# sunbeamB.net
KiCad netlist of a schematic drawn in EAGLE
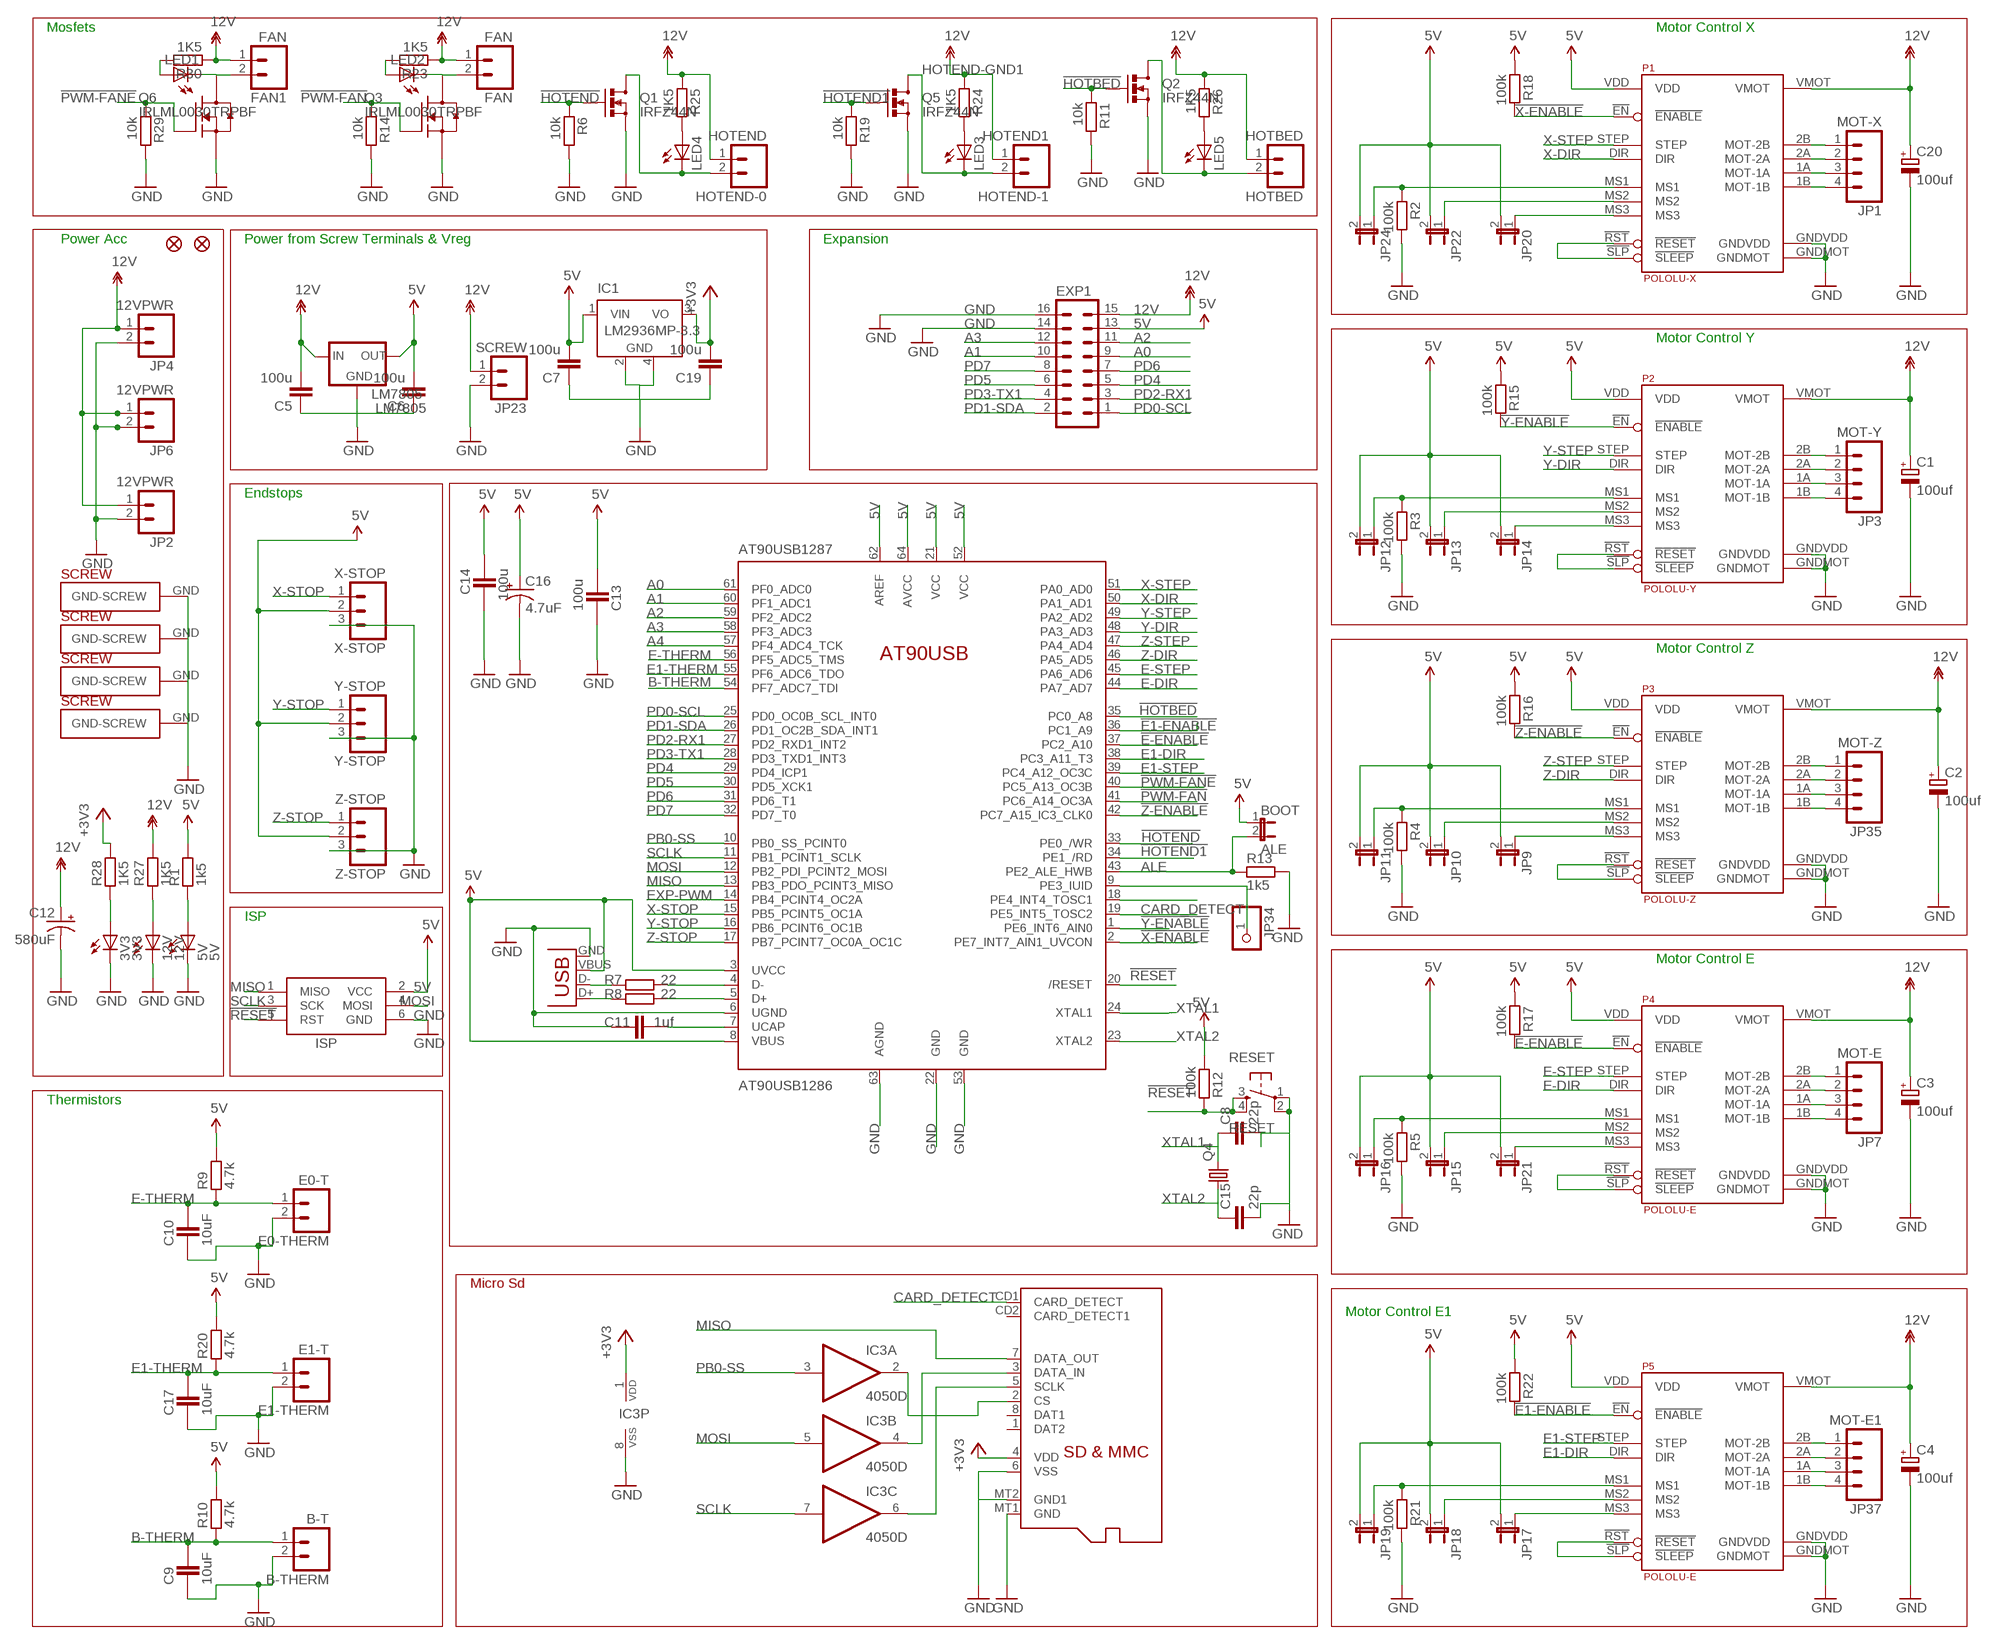
[diagram p0: schematic, sheet 1]

(export (version "E")
  (design (tool "Eeschema 10.0.6"))
  (components
    (comp (ref "3V3")
      (value "3V3")
      (footprint "eagle-import:CHIPLED_0805")
      (libsource (lib "eagle-import") (part "LEDCHIPLED_0805"))
    )
    (comp (ref "5V")
      (value "5V")
      (footprint "eagle-import:CHIPLED_0805")
      (libsource (lib "eagle-import") (part "LEDCHIPLED_0805"))
    )
    (comp (ref "12V")
      (value "12V")
      (footprint "eagle-import:CHIPLED_0805")
      (libsource (lib "eagle-import") (part "LEDCHIPLED_0805"))
    )
    (comp (ref "AT90USB1287")
      (value "AT90USB1286")
      (footprint "eagle-import:TQFP64-2")
      (libsource (lib "eagle-import") (part "AT90USB"))
    )
    (comp (ref "B-THERM")
      (value "B-T")
      (footprint "eagle-import:MOLEX-1X2")
      (libsource (lib "eagle-import") (part "M02POLAR"))
    )
    (comp (ref "BOOT")
      (value "ALE")
      (footprint "eagle-import:1X02")
      (libsource (lib "eagle-import") (part "JUMPER-2PTH"))
    )
    (comp (ref "C1")
      (value "100uf")
      (footprint "eagle-import:UD-6,3X7,7_NICHICON")
      (libsource (lib "eagle-import") (part "CPOL-EUUD-6,3X7,7"))
    )
    (comp (ref "C2")
      (value "100uf")
      (footprint "eagle-import:UD-6,3X7,7_NICHICON")
      (libsource (lib "eagle-import") (part "CPOL-EUUD-6,3X7,7"))
    )
    (comp (ref "C3")
      (value "100uf")
      (footprint "eagle-import:UD-6,3X7,7_NICHICON")
      (libsource (lib "eagle-import") (part "CPOL-EUUD-6,3X7,7"))
    )
    (comp (ref "C4")
      (value "100uf")
      (footprint "eagle-import:UD-6,3X7,7_NICHICON")
      (libsource (lib "eagle-import") (part "CPOL-EUUD-6,3X7,7"))
    )
    (comp (ref "C5")
      (value "100u")
      (footprint "eagle-import:C0805")
      (libsource (lib "eagle-import") (part "C-EUC0805"))
    )
    (comp (ref "C6")
      (value "100u")
      (footprint "eagle-import:C0805")
      (libsource (lib "eagle-import") (part "C-EUC0805"))
    )
    (comp (ref "C7")
      (value "100u")
      (footprint "eagle-import:C0805")
      (libsource (lib "eagle-import") (part "C-EUC0805"))
    )
    (comp (ref "C8")
      (value "22p")
      (footprint "eagle-import:C0805")
      (libsource (lib "eagle-import") (part "C-EUC0805"))
    )
    (comp (ref "C9")
      (value "10uF")
      (footprint "eagle-import:CAPC2012X145AN")
      (libsource (lib "eagle-import") (part "CAPACITOR_0805"))
    )
    (comp (ref "C10")
      (value "10uF")
      (footprint "eagle-import:CAPC2012X145AN")
      (libsource (lib "eagle-import") (part "CAPACITOR_0805"))
    )
    (comp (ref "C11")
      (value "1uf")
      (footprint "eagle-import:CAPC2012X145AN")
      (libsource (lib "eagle-import") (part "CAPACITOR_0805"))
    )
    (comp (ref "C12")
      (value "580uF")
      (footprint "eagle-import:CPOL-RADIAL-1000UF-25V")
      (libsource (lib "eagle-import") (part "CAP_POLPTH4"))
    )
    (comp (ref "C13")
      (value "100u")
      (footprint "eagle-import:CAPC2012X145AN")
      (libsource (lib "eagle-import") (part "CAPACITOR_0805"))
    )
    (comp (ref "C14")
      (value "100u")
      (footprint "eagle-import:CAPC2012X145AN")
      (libsource (lib "eagle-import") (part "CAPACITOR_0805"))
    )
    (comp (ref "C15")
      (value "22p")
      (footprint "eagle-import:C0805")
      (libsource (lib "eagle-import") (part "C-EUC0805"))
    )
    (comp (ref "C16")
      (value "4.7uF")
      (footprint "eagle-import:CPOL-RADIAL-10UF-25V")
      (libsource (lib "eagle-import") (part "CAP_POLPTH2"))
    )
    (comp (ref "C17")
      (value "10uF")
      (footprint "eagle-import:CAPC2012X145AN")
      (libsource (lib "eagle-import") (part "CAPACITOR_0805"))
    )
    (comp (ref "C19")
      (value "100u")
      (footprint "eagle-import:C0805")
      (libsource (lib "eagle-import") (part "C-EUC0805"))
    )
    (comp (ref "C20")
      (value "100uf")
      (footprint "eagle-import:UD-6,3X7,7_NICHICON")
      (libsource (lib "eagle-import") (part "CPOL-EUUD-6,3X7,7"))
    )
    (comp (ref "E0-THERM")
      (value "E0-T")
      (footprint "eagle-import:MOLEX-1X2")
      (libsource (lib "eagle-import") (part "M02POLAR"))
    )
    (comp (ref "E1-THERM")
      (value "E1-T")
      (footprint "eagle-import:MOLEX-1X2")
      (libsource (lib "eagle-import") (part "M02POLAR"))
    )
    (comp (ref "EXP1")
      (value "MA08-2")
      (footprint "eagle-import:MA08-2")
      (libsource (lib "eagle-import") (part "MA08-2"))
    )
    (comp (ref "FAN")
      (value "FAN")
      (footprint "eagle-import:MOLEX-1X2")
      (libsource (lib "eagle-import") (part "M02POLAR"))
    )
    (comp (ref "FAN1")
      (value "FAN")
      (footprint "eagle-import:MOLEX-1X2")
      (libsource (lib "eagle-import") (part "M02POLAR"))
    )
    (comp (ref "HOTBED")
      (value "HOTBED")
      (footprint "eagle-import:SCREWTERMINAL-5MM-2")
      (libsource (lib "eagle-import") (part "M025MM"))
    )
    (comp (ref "HOTEND-0")
      (value "HOTEND")
      (footprint "eagle-import:SCREWTERMINAL-5MM-2")
      (libsource (lib "eagle-import") (part "M025MM"))
    )
    (comp (ref "HOTEND-1")
      (value "HOTEND1")
      (footprint "eagle-import:SCREWTERMINAL-5MM-2")
      (libsource (lib "eagle-import") (part "M025MM"))
    )
    (comp (ref "IC1")
      (value "LM2936MP-3.3")
      (footprint "eagle-import:SOT223")
      (fields (field (name "MF") "NATIONAL SEMICONDUCTOR") (field (name "MPN") "LM2936MP-3.3/NOPB"))
      (libsource (lib "eagle-import") (part "LM2936MP?-3.3"))
    )
    (comp (ref "IC3")
      (value "4050D")
      (footprint "eagle-import:SO16")
      (libsource (lib "eagle-import") (part "4050D"))
    )
    (comp (ref "ISP")
      (value "ISP")
      (footprint "eagle-import:AVRISP")
      (libsource (lib "eagle-import") (part "AVRISP-6"))
    )
    (comp (ref "J1")
      (value "USB")
      (footprint "eagle-import:USB-B-PTH")
      (libsource (lib "eagle-import") (part "USBPTH"))
    )
    (comp (ref "JP1")
      (value "MOT-X")
      (footprint "eagle-import:MOLEX-1X4")
      (libsource (lib "eagle-import") (part "M04POLAR"))
    )
    (comp (ref "JP2")
      (value "12VPWR")
      (footprint "eagle-import:MOLEX-1X2")
      (libsource (lib "eagle-import") (part "M02POLAR"))
    )
    (comp (ref "JP3")
      (value "MOT-Y")
      (footprint "eagle-import:MOLEX-1X4")
      (libsource (lib "eagle-import") (part "M04POLAR"))
    )
    (comp (ref "JP4")
      (value "12VPWR")
      (footprint "eagle-import:MOLEX-1X2")
      (libsource (lib "eagle-import") (part "M02POLAR"))
    )
    (comp (ref "JP5")
      (value "FIDUCIAL1X2.5")
      (footprint "eagle-import:FIDUCIAL-1X2.5")
      (libsource (lib "eagle-import") (part "FIDUCIAL1X2.5"))
    )
    (comp (ref "JP6")
      (value "12VPWR")
      (footprint "eagle-import:MOLEX-1X2")
      (libsource (lib "eagle-import") (part "M02POLAR"))
    )
    (comp (ref "JP7")
      (value "MOT-E")
      (footprint "eagle-import:MOLEX-1X4")
      (libsource (lib "eagle-import") (part "M04POLAR"))
    )
    (comp (ref "JP8")
      (value "FIDUCIAL1X2.5")
      (footprint "eagle-import:FIDUCIAL-1X2.5")
      (libsource (lib "eagle-import") (part "FIDUCIAL1X2.5"))
    )
    (comp (ref "JP9")
      (value "JUMPER-2-OLDSMD-NO")
      (footprint "eagle-import:SJ_2S-NO")
      (libsource (lib "eagle-import") (part "JUMPER-2-OLDSMD-NO"))
    )
    (comp (ref "JP10")
      (value "JUMPER-2-OLDSMD-NO")
      (footprint "eagle-import:SJ_2S-NO")
      (libsource (lib "eagle-import") (part "JUMPER-2-OLDSMD-NO"))
    )
    (comp (ref "JP11")
      (value "JUMPER-2-OLDSMD-NO")
      (footprint "eagle-import:SJ_2S-NO")
      (libsource (lib "eagle-import") (part "JUMPER-2-OLDSMD-NO"))
    )
    (comp (ref "JP12")
      (value "JUMPER-2-OLDSMD-NO")
      (footprint "eagle-import:SJ_2S-NO")
      (libsource (lib "eagle-import") (part "JUMPER-2-OLDSMD-NO"))
    )
    (comp (ref "JP13")
      (value "JUMPER-2-OLDSMD-NO")
      (footprint "eagle-import:SJ_2S-NO")
      (libsource (lib "eagle-import") (part "JUMPER-2-OLDSMD-NO"))
    )
    (comp (ref "JP14")
      (value "JUMPER-2-OLDSMD-NO")
      (footprint "eagle-import:SJ_2S-NO")
      (libsource (lib "eagle-import") (part "JUMPER-2-OLDSMD-NO"))
    )
    (comp (ref "JP15")
      (value "JUMPER-2-OLDSMD-NO")
      (footprint "eagle-import:SJ_2S-NO")
      (libsource (lib "eagle-import") (part "JUMPER-2-OLDSMD-NO"))
    )
    (comp (ref "JP16")
      (value "JUMPER-2-OLDSMD-NO")
      (footprint "eagle-import:SJ_2S-NO")
      (libsource (lib "eagle-import") (part "JUMPER-2-OLDSMD-NO"))
    )
    (comp (ref "JP17")
      (value "JUMPER-2-OLDSMD-NO")
      (footprint "eagle-import:SJ_2S-NO")
      (libsource (lib "eagle-import") (part "JUMPER-2-OLDSMD-NO"))
    )
    (comp (ref "JP18")
      (value "JUMPER-2-OLDSMD-NO")
      (footprint "eagle-import:SJ_2S-NO")
      (libsource (lib "eagle-import") (part "JUMPER-2-OLDSMD-NO"))
    )
    (comp (ref "JP19")
      (value "JUMPER-2-OLDSMD-NO")
      (footprint "eagle-import:SJ_2S-NO")
      (libsource (lib "eagle-import") (part "JUMPER-2-OLDSMD-NO"))
    )
    (comp (ref "JP20")
      (value "JUMPER-2-OLDSMD-NO")
      (footprint "eagle-import:SJ_2S-NO")
      (libsource (lib "eagle-import") (part "JUMPER-2-OLDSMD-NO"))
    )
    (comp (ref "JP21")
      (value "JUMPER-2-OLDSMD-NO")
      (footprint "eagle-import:SJ_2S-NO")
      (libsource (lib "eagle-import") (part "JUMPER-2-OLDSMD-NO"))
    )
    (comp (ref "JP22")
      (value "JUMPER-2-OLDSMD-NO")
      (footprint "eagle-import:SJ_2S-NO")
      (libsource (lib "eagle-import") (part "JUMPER-2-OLDSMD-NO"))
    )
    (comp (ref "JP23")
      (value "SCREW")
      (footprint "eagle-import:SCREWTERMINAL-5MM-2")
      (libsource (lib "eagle-import") (part "M025MM"))
    )
    (comp (ref "JP24")
      (value "JUMPER-2-OLDSMD-NO")
      (footprint "eagle-import:SJ_2S-NO")
      (libsource (lib "eagle-import") (part "JUMPER-2-OLDSMD-NO"))
    )
    (comp (ref "JP34")
      (value "PINHD-1X1")
      (footprint "eagle-import:1X01")
      (libsource (lib "eagle-import") (part "PINHD-1X1"))
    )
    (comp (ref "JP35")
      (value "MOT-Z")
      (footprint "eagle-import:MOLEX-1X4")
      (libsource (lib "eagle-import") (part "M04POLAR"))
    )
    (comp (ref "JP37")
      (value "MOT-E1")
      (footprint "eagle-import:MOLEX-1X4")
      (libsource (lib "eagle-import") (part "M04POLAR"))
    )
    (comp (ref "LED1")
      (value "LEDCHIPLED_0805")
      (footprint "eagle-import:CHIPLED_0805")
      (libsource (lib "eagle-import") (part "LEDCHIPLED_0805"))
    )
    (comp (ref "LED2")
      (value "LEDCHIPLED_0805")
      (footprint "eagle-import:CHIPLED_0805")
      (libsource (lib "eagle-import") (part "LEDCHIPLED_0805"))
    )
    (comp (ref "LED3")
      (value "LEDCHIPLED_0805")
      (footprint "eagle-import:CHIPLED_0805")
      (libsource (lib "eagle-import") (part "LEDCHIPLED_0805"))
    )
    (comp (ref "LED4")
      (value "LEDCHIPLED_0805")
      (footprint "eagle-import:CHIPLED_0805")
      (libsource (lib "eagle-import") (part "LEDCHIPLED_0805"))
    )
    (comp (ref "LED5")
      (value "LEDCHIPLED_0805")
      (footprint "eagle-import:CHIPLED_0805")
      (libsource (lib "eagle-import") (part "LEDCHIPLED_0805"))
    )
    (comp (ref "LM7805")
      (value "LM7805")
      (footprint "eagle-import:78XXL-CUSTOM")
      (libsource (lib "eagle-import") (part "V_REG_78XX"))
    )
    (comp (ref "MICRO-SD")
      (value "MICROSD")
      (footprint "eagle-import:MICROSD")
      (libsource (lib "eagle-import") (part "MICROSD"))
    )
    (comp (ref "P1")
      (value "POLOLU-X")
      (footprint "eagle-import:POLOLU-ALLEGRO-PTH")
      (libsource (lib "eagle-import") (part "POLOLU-ALLEGRO"))
    )
    (comp (ref "P2")
      (value "POLOLU-Y")
      (footprint "eagle-import:POLOLU-ALLEGRO-PTH")
      (libsource (lib "eagle-import") (part "POLOLU-ALLEGRO"))
    )
    (comp (ref "P3")
      (value "POLOLU-Z")
      (footprint "eagle-import:POLOLU-ALLEGRO-PTH")
      (libsource (lib "eagle-import") (part "POLOLU-ALLEGRO"))
    )
    (comp (ref "P4")
      (value "POLOLU-E")
      (footprint "eagle-import:POLOLU-ALLEGRO-PTH")
      (libsource (lib "eagle-import") (part "POLOLU-ALLEGRO"))
    )
    (comp (ref "P5")
      (value "POLOLU-E")
      (footprint "eagle-import:POLOLU-ALLEGRO-PTH")
      (libsource (lib "eagle-import") (part "POLOLU-ALLEGRO"))
    )
    (comp (ref "Q1")
      (value "IRFZ44N")
      (footprint "eagle-import:TO220V")
      (libsource (lib "eagle-import") (part "MOSFET-NCHANNELPTH2"))
    )
    (comp (ref "Q2")
      (value "IRFZ44N")
      (footprint "eagle-import:TO220V")
      (libsource (lib "eagle-import") (part "MOSFET-NCHANNELPTH2"))
    )
    (comp (ref "Q3")
      (value "IRLML0030TRPBF")
      (footprint "eagle-import:SOT95P280X135-3N")
      (libsource (lib "eagle-import") (part "MOSFET-NCH_SOT-23"))
    )
    (comp (ref "Q4")
      (value "CRYSTALHC49UP")
      (footprint "eagle-import:HC49UP")
      (libsource (lib "eagle-import") (part "CRYSTALHC49UP"))
    )
    (comp (ref "Q5")
      (value "IRFZ44N")
      (footprint "eagle-import:TO220V")
      (libsource (lib "eagle-import") (part "MOSFET-NCHANNELPTH2"))
    )
    (comp (ref "Q6")
      (value "IRLML0030TRPBF")
      (footprint "eagle-import:SOT95P280X135-3N")
      (libsource (lib "eagle-import") (part "MOSFET-NCH_SOT-23"))
    )
    (comp (ref "R1")
      (value "1k5")
      (footprint "eagle-import:RESC2012X70N")
      (libsource (lib "eagle-import") (part "RESISTOR_0805"))
    )
    (comp (ref "R2")
      (value "100k")
      (footprint "eagle-import:RESC2012X70N")
      (libsource (lib "eagle-import") (part "RESISTOR_0805"))
    )
    (comp (ref "R3")
      (value "100k")
      (footprint "eagle-import:RESC2012X70N")
      (libsource (lib "eagle-import") (part "RESISTOR_0805"))
    )
    (comp (ref "R4")
      (value "100k")
      (footprint "eagle-import:RESC2012X70N")
      (libsource (lib "eagle-import") (part "RESISTOR_0805"))
    )
    (comp (ref "R5")
      (value "100k")
      (footprint "eagle-import:RESC2012X70N")
      (libsource (lib "eagle-import") (part "RESISTOR_0805"))
    )
    (comp (ref "R6")
      (value "10k")
      (footprint "eagle-import:RESC2012X70N")
      (libsource (lib "eagle-import") (part "RESISTOR_0805"))
    )
    (comp (ref "R7")
      (value "22")
      (footprint "eagle-import:RESC2012X70N")
      (libsource (lib "eagle-import") (part "RESISTOR_0805"))
    )
    (comp (ref "R8")
      (value "22")
      (footprint "eagle-import:RESC2012X70N")
      (libsource (lib "eagle-import") (part "RESISTOR_0805"))
    )
    (comp (ref "R9")
      (value "4.7k")
      (footprint "eagle-import:RESC2012X70N")
      (libsource (lib "eagle-import") (part "RESISTOR_0805"))
    )
    (comp (ref "R10")
      (value "4.7k")
      (footprint "eagle-import:RESC2012X70N")
      (libsource (lib "eagle-import") (part "RESISTOR_0805"))
    )
    (comp (ref "R11")
      (value "10k")
      (footprint "eagle-import:RESC2012X70N")
      (libsource (lib "eagle-import") (part "RESISTOR_0805"))
    )
    (comp (ref "R12")
      (value "100k")
      (footprint "eagle-import:RESC2012X70N")
      (libsource (lib "eagle-import") (part "RESISTOR_0805"))
    )
    (comp (ref "R13")
      (value "1k5")
      (footprint "eagle-import:RESC2012X70N")
      (libsource (lib "eagle-import") (part "RESISTOR_0805"))
    )
    (comp (ref "R14")
      (value "10k")
      (footprint "eagle-import:RESC2012X70N")
      (libsource (lib "eagle-import") (part "RESISTOR_0805"))
    )
    (comp (ref "R15")
      (value "100k")
      (footprint "eagle-import:RESC2012X70N")
      (libsource (lib "eagle-import") (part "RESISTOR_0805"))
    )
    (comp (ref "R16")
      (value "100k")
      (footprint "eagle-import:RESC2012X70N")
      (libsource (lib "eagle-import") (part "RESISTOR_0805"))
    )
    (comp (ref "R17")
      (value "100k")
      (footprint "eagle-import:RESC2012X70N")
      (libsource (lib "eagle-import") (part "RESISTOR_0805"))
    )
    (comp (ref "R18")
      (value "100k")
      (footprint "eagle-import:RESC2012X70N")
      (libsource (lib "eagle-import") (part "RESISTOR_0805"))
    )
    (comp (ref "R19")
      (value "10k")
      (footprint "eagle-import:RESC2012X70N")
      (libsource (lib "eagle-import") (part "RESISTOR_0805"))
    )
    (comp (ref "R20")
      (value "4.7k")
      (footprint "eagle-import:RESC2012X70N")
      (libsource (lib "eagle-import") (part "RESISTOR_0805"))
    )
    (comp (ref "R21")
      (value "100k")
      (footprint "eagle-import:RESC2012X70N")
      (libsource (lib "eagle-import") (part "RESISTOR_0805"))
    )
    (comp (ref "R22")
      (value "100k")
      (footprint "eagle-import:RESC2012X70N")
      (libsource (lib "eagle-import") (part "RESISTOR_0805"))
    )
    (comp (ref "R23")
      (value "1K5")
      (footprint "eagle-import:RESC2012X70N")
      (libsource (lib "eagle-import") (part "RESISTOR_0805"))
    )
    (comp (ref "R24")
      (value "1K5")
      (footprint "eagle-import:RESC2012X70N")
      (libsource (lib "eagle-import") (part "RESISTOR_0805"))
    )
    (comp (ref "R25")
      (value "1K5")
      (footprint "eagle-import:RESC2012X70N")
      (libsource (lib "eagle-import") (part "RESISTOR_0805"))
    )
    (comp (ref "R26")
      (value "1K5")
      (footprint "eagle-import:RESC2012X70N")
      (libsource (lib "eagle-import") (part "RESISTOR_0805"))
    )
    (comp (ref "R27")
      (value "1K5")
      (footprint "eagle-import:RESC2012X70N")
      (libsource (lib "eagle-import") (part "RESISTOR_0805"))
    )
    (comp (ref "R28")
      (value "1K5")
      (footprint "eagle-import:RESC2012X70N")
      (libsource (lib "eagle-import") (part "RESISTOR_0805"))
    )
    (comp (ref "R29")
      (value "10k")
      (footprint "eagle-import:RESC2012X70N")
      (libsource (lib "eagle-import") (part "RESISTOR_0805"))
    )
    (comp (ref "R30")
      (value "1K5")
      (footprint "eagle-import:RESC2012X70N")
      (libsource (lib "eagle-import") (part "RESISTOR_0805"))
    )
    (comp (ref "RESET")
      (value "RESET")
      (footprint "eagle-import:TACTILE-PTH")
      (libsource (lib "eagle-import") (part "TAC_SWITCHPTH"))
    )
    (comp (ref "U$47")
      (value "PLATED-SCREW")
      (footprint "eagle-import:PLATEDSCREW")
      (libsource (lib "eagle-import") (part "PLATED-SCREW"))
    )
    (comp (ref "U$48")
      (value "PLATED-SCREW")
      (footprint "eagle-import:PLATEDSCREW")
      (libsource (lib "eagle-import") (part "PLATED-SCREW"))
    )
    (comp (ref "U$49")
      (value "PLATED-SCREW")
      (footprint "eagle-import:PLATEDSCREW")
      (libsource (lib "eagle-import") (part "PLATED-SCREW"))
    )
    (comp (ref "U$50")
      (value "PLATED-SCREW")
      (footprint "eagle-import:PLATEDSCREW")
      (libsource (lib "eagle-import") (part "PLATED-SCREW"))
    )
    (comp (ref "X-STOP")
      (value "X-STOP")
      (footprint "eagle-import:MOLEX-1X3")
      (libsource (lib "eagle-import") (part "M03POLAR"))
    )
    (comp (ref "Y-STOP")
      (value "Y-STOP")
      (footprint "eagle-import:MOLEX-1X3")
      (libsource (lib "eagle-import") (part "M03POLAR"))
    )
    (comp (ref "Z-STOP")
      (value "Z-STOP")
      (footprint "eagle-import:MOLEX-1X3")
      (libsource (lib "eagle-import") (part "M03POLAR"))
    )
  )
  (nets
    (net (code "1") (name "+3V3") (class "Default")
      (node (ref "C19") (pin "2") (pinfunction "2_2") (pintype "passive"))
      (node (ref "IC1") (pin "3") (pinfunction "VO_3") (pintype "passive"))
      (node (ref "IC3") (pin "1") (pinfunction "VDD_1") (pintype "power_in"))
      (node (ref "MICRO-SD") (pin "4") (pinfunction "VDD_4") (pintype "power_in"))
      (node (ref "R28") (pin "2") (pinfunction "2_2") (pintype "passive"))
    )
    (net (code "2") (name "/A0") (class "Default")
      (node (ref "AT90USB1287") (pin "61") (pinfunction "PF0_ADC0_61") (pintype "bidirectional"))
      (node (ref "EXP1") (pin "9") (pinfunction "9_9") (pintype "passive"))
    )
    (net (code "3") (name "/A1") (class "Default")
      (node (ref "AT90USB1287") (pin "60") (pinfunction "PF1_ADC1_60") (pintype "bidirectional"))
      (node (ref "EXP1") (pin "10") (pinfunction "10_10") (pintype "passive"))
    )
    (net (code "4") (name "/A2") (class "Default")
      (node (ref "AT90USB1287") (pin "59") (pinfunction "PF2_ADC2_59") (pintype "bidirectional"))
      (node (ref "EXP1") (pin "11") (pinfunction "11_11") (pintype "passive"))
    )
    (net (code "5") (name "/A3") (class "Default")
      (node (ref "AT90USB1287") (pin "58") (pinfunction "PF3_ADC3_58") (pintype "bidirectional"))
      (node (ref "EXP1") (pin "12") (pinfunction "12_12") (pintype "passive"))
    )
    (net (code "6") (name "/A4") (class "Default")
      (node (ref "AT90USB1287") (pin "57") (pinfunction "PF4_ADC4_TCK_57") (pintype "bidirectional"))
    )
    (net (code "7") (name "/ALE") (class "Default")
      (node (ref "AT90USB1287") (pin "43") (pinfunction "PE2_ALE_HWB_43") (pintype "bidirectional"))
      (node (ref "BOOT") (pin "2") (pinfunction "2_2") (pintype "passive"))
      (node (ref "R13") (pin "1") (pinfunction "1_1") (pintype "passive"))
    )
    (net (code "8") (name "/B-THERM") (class "Default")
      (node (ref "AT90USB1287") (pin "54") (pinfunction "PF7_ADC7_TDI_54") (pintype "bidirectional"))
      (node (ref "B-THERM") (pin "1") (pinfunction "1_1") (pintype "passive"))
      (node (ref "C9") (pin "2") (pinfunction "2_2") (pintype "passive"))
      (node (ref "R10") (pin "1") (pinfunction "1_1") (pintype "passive"))
    )
    (net (code "9") (name "/CARD_DETECT") (class "Default")
      (node (ref "AT90USB1287") (pin "19") (pinfunction "PE5_INT5_TOSC2_19") (pintype "bidirectional"))
      (node (ref "MICRO-SD") (pin "CD1") (pinfunction "CARD_DETECT_CD1") (pintype "passive"))
    )
    (net (code "10") (name "/E-DIR") (class "Default")
      (node (ref "AT90USB1287") (pin "44") (pinfunction "PA7_AD7_44") (pintype "bidirectional"))
      (node (ref "P4") (pin "DIR") (pinfunction "DIR_DIR") (pintype "bidirectional"))
    )
    (net (code "11") (name "/E-STEP") (class "Default")
      (node (ref "AT90USB1287") (pin "45") (pinfunction "PA6_AD6_45") (pintype "bidirectional"))
      (node (ref "P4") (pin "STEP") (pinfunction "STEP_STEP") (pintype "bidirectional"))
    )
    (net (code "12") (name "/E-THERM") (class "Default")
      (node (ref "AT90USB1287") (pin "56") (pinfunction "PF5_ADC5_TMS_56") (pintype "bidirectional"))
      (node (ref "C10") (pin "2") (pinfunction "2_2") (pintype "passive"))
      (node (ref "E0-THERM") (pin "1") (pinfunction "1_1") (pintype "passive"))
      (node (ref "R9") (pin "1") (pinfunction "1_1") (pintype "passive"))
    )
    (net (code "13") (name "/E1-DIR") (class "Default")
      (node (ref "AT90USB1287") (pin "38") (pinfunction "PC3_A11_T3_38") (pintype "bidirectional"))
      (node (ref "P5") (pin "DIR") (pinfunction "DIR_DIR") (pintype "bidirectional"))
    )
    (net (code "14") (name "/E1-STEP") (class "Default")
      (node (ref "AT90USB1287") (pin "39") (pinfunction "PC4_A12_OC3C_39") (pintype "bidirectional"))
      (node (ref "P5") (pin "STEP") (pinfunction "STEP_STEP") (pintype "bidirectional"))
    )
    (net (code "15") (name "/E1-THERM") (class "Default")
      (node (ref "AT90USB1287") (pin "55") (pinfunction "PF6_ADC6_TDO_55") (pintype "bidirectional"))
      (node (ref "C17") (pin "2") (pinfunction "2_2") (pintype "passive"))
      (node (ref "E1-THERM") (pin "1") (pinfunction "1_1") (pintype "passive"))
      (node (ref "R20") (pin "1") (pinfunction "1_1") (pintype "passive"))
    )
    (net (code "16") (name "/EXP-PWM") (class "Default")
      (node (ref "AT90USB1287") (pin "14") (pinfunction "PB4_PCINT4_OC2A_14") (pintype "bidirectional"))
    )
    (net (code "17") (name "/HOTEND-GND1") (class "Default")
      (node (ref "HOTEND-1") (pin "2") (pinfunction "2_2") (pintype "passive"))
      (node (ref "LED3") (pin "C") (pinfunction "C_C") (pintype "passive"))
      (node (ref "Q5") (pin "2") (pinfunction "D_2") (pintype "passive"))
    )
    (net (code "18") (name "/MISO") (class "Default")
      (node (ref "AT90USB1287") (pin "13") (pinfunction "PB3_PDO_PCINT3_MISO_13") (pintype "bidirectional"))
      (node (ref "ISP") (pin "1") (pinfunction "MISO_1") (pintype "input"))
      (node (ref "MICRO-SD") (pin "7") (pinfunction "DATA_OUT_7") (pintype "output"))
    )
    (net (code "19") (name "/MOSI") (class "Default")
      (node (ref "AT90USB1287") (pin "12") (pinfunction "PB2_PDI_PCINT2_MOSI_12") (pintype "bidirectional"))
      (node (ref "IC3") (pin "5") (pinfunction "I_5") (pintype "input"))
      (node (ref "ISP") (pin "4") (pinfunction "MOSI_4") (pintype "output"))
    )
    (net (code "20") (name "/PB0-SS") (class "Default")
      (node (ref "AT90USB1287") (pin "10") (pinfunction "PB0_SS_PCINT0_10") (pintype "bidirectional"))
      (node (ref "IC3") (pin "3") (pinfunction "I_3") (pintype "input"))
    )
    (net (code "21") (name "/PD0-SCL") (class "Default")
      (node (ref "AT90USB1287") (pin "25") (pinfunction "PD0_OC0B_SCL_INT0_25") (pintype "bidirectional"))
      (node (ref "EXP1") (pin "1") (pinfunction "1_1") (pintype "passive"))
    )
    (net (code "22") (name "/PD1-SDA") (class "Default")
      (node (ref "AT90USB1287") (pin "26") (pinfunction "PD1_OC2B_SDA_INT1_26") (pintype "bidirectional"))
      (node (ref "EXP1") (pin "2") (pinfunction "2_2") (pintype "passive"))
    )
    (net (code "23") (name "/PD2-RX1") (class "Default")
      (node (ref "AT90USB1287") (pin "27") (pinfunction "PD2_RXD1_INT2_27") (pintype "bidirectional"))
      (node (ref "EXP1") (pin "3") (pinfunction "3_3") (pintype "passive"))
    )
    (net (code "24") (name "/PD3-TX1") (class "Default")
      (node (ref "AT90USB1287") (pin "28") (pinfunction "PD3_TXD1_INT3_28") (pintype "bidirectional"))
      (node (ref "EXP1") (pin "4") (pinfunction "4_4") (pintype "passive"))
    )
    (net (code "25") (name "/PD4") (class "Default")
      (node (ref "AT90USB1287") (pin "29") (pinfunction "PD4_ICP1_29") (pintype "bidirectional"))
      (node (ref "EXP1") (pin "5") (pinfunction "5_5") (pintype "passive"))
    )
    (net (code "26") (name "/PD5") (class "Default")
      (node (ref "AT90USB1287") (pin "30") (pinfunction "PD5_XCK1_30") (pintype "bidirectional"))
      (node (ref "EXP1") (pin "6") (pinfunction "6_6") (pintype "passive"))
    )
    (net (code "27") (name "/PD6") (class "Default")
      (node (ref "AT90USB1287") (pin "31") (pinfunction "PD6_T1_31") (pintype "bidirectional"))
      (node (ref "EXP1") (pin "7") (pinfunction "7_7") (pintype "passive"))
    )
    (net (code "28") (name "/PD7") (class "Default")
      (node (ref "AT90USB1287") (pin "32") (pinfunction "PD7_T0_32") (pintype "bidirectional"))
      (node (ref "EXP1") (pin "8") (pinfunction "8_8") (pintype "passive"))
    )
    (net (code "29") (name "/SCLK") (class "Default")
      (node (ref "AT90USB1287") (pin "11") (pinfunction "PB1_PCINT1_SCLK_11") (pintype "bidirectional"))
      (node (ref "IC3") (pin "7") (pinfunction "I_7") (pintype "input"))
      (node (ref "ISP") (pin "3") (pinfunction "SCK_3") (pintype "output"))
    )
    (net (code "30") (name "/X-DIR") (class "Default")
      (node (ref "AT90USB1287") (pin "50") (pinfunction "PA1_AD1_50") (pintype "bidirectional"))
      (node (ref "P1") (pin "DIR") (pinfunction "DIR_DIR") (pintype "bidirectional"))
    )
    (net (code "31") (name "/X-STEP") (class "Default")
      (node (ref "AT90USB1287") (pin "51") (pinfunction "PA0_AD0_51") (pintype "bidirectional"))
      (node (ref "P1") (pin "STEP") (pinfunction "STEP_STEP") (pintype "bidirectional"))
    )
    (net (code "32") (name "/X-STOP") (class "Default")
      (node (ref "AT90USB1287") (pin "15") (pinfunction "PB5_PCINT5_OC1A_15") (pintype "bidirectional"))
      (node (ref "X-STOP") (pin "1") (pinfunction "1_1") (pintype "passive"))
    )
    (net (code "33") (name "/XTAL1") (class "Default")
      (node (ref "AT90USB1287") (pin "24") (pinfunction "XTAL1_24") (pintype "passive"))
      (node (ref "C8") (pin "1") (pinfunction "1_1") (pintype "passive"))
      (node (ref "Q4") (pin "2") (pinfunction "2_2") (pintype "passive"))
    )
    (net (code "34") (name "/XTAL2") (class "Default")
      (node (ref "AT90USB1287") (pin "23") (pinfunction "XTAL2_23") (pintype "passive"))
      (node (ref "C15") (pin "1") (pinfunction "1_1") (pintype "passive"))
      (node (ref "Q4") (pin "1") (pinfunction "1_1") (pintype "passive"))
    )
    (net (code "35") (name "/Y-DIR") (class "Default")
      (node (ref "AT90USB1287") (pin "48") (pinfunction "PA3_AD3_48") (pintype "bidirectional"))
      (node (ref "P2") (pin "DIR") (pinfunction "DIR_DIR") (pintype "bidirectional"))
    )
    (net (code "36") (name "/Y-STEP") (class "Default")
      (node (ref "AT90USB1287") (pin "49") (pinfunction "PA2_AD2_49") (pintype "bidirectional"))
      (node (ref "P2") (pin "STEP") (pinfunction "STEP_STEP") (pintype "bidirectional"))
    )
    (net (code "37") (name "/Y-STOP") (class "Default")
      (node (ref "AT90USB1287") (pin "16") (pinfunction "PB6_PCINT6_OC1B_16") (pintype "bidirectional"))
      (node (ref "Y-STOP") (pin "1") (pinfunction "1_1") (pintype "passive"))
    )
    (net (code "38") (name "/Z-DIR") (class "Default")
      (node (ref "AT90USB1287") (pin "46") (pinfunction "PA5_AD5_46") (pintype "bidirectional"))
      (node (ref "P3") (pin "DIR") (pinfunction "DIR_DIR") (pintype "bidirectional"))
    )
    (net (code "39") (name "/Z-STEP") (class "Default")
      (node (ref "AT90USB1287") (pin "47") (pinfunction "PA4_AD4_47") (pintype "bidirectional"))
      (node (ref "P3") (pin "STEP") (pinfunction "STEP_STEP") (pintype "bidirectional"))
    )
    (net (code "40") (name "/Z-STOP") (class "Default")
      (node (ref "AT90USB1287") (pin "17") (pinfunction "PB7_PCINT7_OC0A_OC1C_17") (pintype "bidirectional"))
      (node (ref "Z-STOP") (pin "1") (pinfunction "1_1") (pintype "passive"))
    )
    (net (code "41") (name "/~{E-ENABLE}") (class "Default")
      (node (ref "AT90USB1287") (pin "37") (pinfunction "PC2_A10_37") (pintype "bidirectional"))
      (node (ref "P4") (pin "!EN") (pinfunction "~{ENABLE}_!EN") (pintype "input"))
      (node (ref "R17") (pin "2") (pinfunction "2_2") (pintype "passive"))
    )
    (net (code "42") (name "/~{E1-ENABLE}") (class "Default")
      (node (ref "AT90USB1287") (pin "36") (pinfunction "PC1_A9_36") (pintype "bidirectional"))
      (node (ref "P5") (pin "!EN") (pinfunction "~{ENABLE}_!EN") (pintype "input"))
      (node (ref "R22") (pin "2") (pinfunction "2_2") (pintype "passive"))
    )
    (net (code "43") (name "/~{HOTBED}") (class "Default")
      (node (ref "AT90USB1287") (pin "35") (pinfunction "PC0_A8_35") (pintype "bidirectional"))
      (node (ref "Q2") (pin "1") (pinfunction "G_1") (pintype "passive"))
      (node (ref "R11") (pin "1") (pinfunction "1_1") (pintype "passive"))
    )
    (net (code "44") (name "/~{HOTEND1}") (class "Default")
      (node (ref "AT90USB1287") (pin "34") (pinfunction "PE1_/RD_34") (pintype "bidirectional"))
      (node (ref "Q5") (pin "1") (pinfunction "G_1") (pintype "passive"))
      (node (ref "R19") (pin "1") (pinfunction "1_1") (pintype "passive"))
    )
    (net (code "45") (name "/~{HOTEND}") (class "Default")
      (node (ref "AT90USB1287") (pin "33") (pinfunction "PE0_/WR_33") (pintype "bidirectional"))
      (node (ref "Q1") (pin "1") (pinfunction "G_1") (pintype "passive"))
      (node (ref "R6") (pin "1") (pinfunction "1_1") (pintype "passive"))
    )
    (net (code "46") (name "/~{PWM-FANE}") (class "Default")
      (node (ref "AT90USB1287") (pin "40") (pinfunction "PC5_A13_OC3B_40") (pintype "bidirectional"))
      (node (ref "Q6") (pin "1") (pinfunction "G_1") (pintype "passive"))
      (node (ref "R29") (pin "1") (pinfunction "1_1") (pintype "passive"))
    )
    (net (code "47") (name "/~{PWM-FAN}") (class "Default")
      (node (ref "AT90USB1287") (pin "41") (pinfunction "PC6_A14_OC3A_41") (pintype "bidirectional"))
      (node (ref "Q3") (pin "1") (pinfunction "G_1") (pintype "passive"))
      (node (ref "R14") (pin "1") (pinfunction "1_1") (pintype "passive"))
    )
    (net (code "48") (name "/~{RESET}") (class "Default")
      (node (ref "AT90USB1287") (pin "20") (pinfunction "/RESET_20") (pintype "bidirectional"))
      (node (ref "ISP") (pin "5") (pinfunction "RST_5") (pintype "output"))
      (node (ref "R12") (pin "1") (pinfunction "1_1") (pintype "passive"))
      (node (ref "RESET") (pin "3") (pinfunction "3_3") (pintype "passive"))
      (node (ref "RESET") (pin "4") (pinfunction "4_4") (pintype "passive"))
    )
    (net (code "49") (name "/~{X-ENABLE}") (class "Default")
      (node (ref "AT90USB1287") (pin "2") (pinfunction "PE7_INT7_AIN1_UVCON_2") (pintype "bidirectional"))
      (node (ref "P1") (pin "!EN") (pinfunction "~{ENABLE}_!EN") (pintype "input"))
      (node (ref "R18") (pin "2") (pinfunction "2_2") (pintype "passive"))
    )
    (net (code "50") (name "/~{Y-ENABLE}") (class "Default")
      (node (ref "AT90USB1287") (pin "1") (pinfunction "PE6_INT6_AIN0_1") (pintype "bidirectional"))
      (node (ref "P2") (pin "!EN") (pinfunction "~{ENABLE}_!EN") (pintype "input"))
      (node (ref "R15") (pin "2") (pinfunction "2_2") (pintype "passive"))
    )
    (net (code "51") (name "/~{Z-ENABLE}") (class "Default")
      (node (ref "AT90USB1287") (pin "42") (pinfunction "PC7_A15_IC3_CLK0_42") (pintype "bidirectional"))
      (node (ref "P3") (pin "!EN") (pinfunction "~{ENABLE}_!EN") (pintype "input"))
      (node (ref "R16") (pin "2") (pinfunction "2_2") (pintype "passive"))
    )
    (net (code "52") (name "5V") (class "Default")
      (node (ref "AT90USB1287") (pin "21") (pinfunction "VCC_21") (pintype "power_in"))
      (node (ref "AT90USB1287") (pin "3") (pinfunction "UVCC_3") (pintype "power_in"))
      (node (ref "AT90USB1287") (pin "52") (pinfunction "VCC_52") (pintype "power_in"))
      (node (ref "AT90USB1287") (pin "62") (pinfunction "AREF_62") (pintype "power_in"))
      (node (ref "AT90USB1287") (pin "64") (pinfunction "AVCC_64") (pintype "power_in"))
      (node (ref "AT90USB1287") (pin "8") (pinfunction "VBUS_8") (pintype "bidirectional"))
      (node (ref "BOOT") (pin "1") (pinfunction "1_1") (pintype "passive"))
      (node (ref "C13") (pin "2") (pinfunction "2_2") (pintype "passive"))
      (node (ref "C14") (pin "1") (pinfunction "1_1") (pintype "passive"))
      (node (ref "C16") (pin "1") (pinfunction "+_1") (pintype "passive"))
      (node (ref "C6") (pin "2") (pinfunction "2_2") (pintype "passive"))
      (node (ref "C7") (pin "2") (pinfunction "2_2") (pintype "passive"))
      (node (ref "EXP1") (pin "13") (pinfunction "13_13") (pintype "passive"))
      (node (ref "IC1") (pin "1") (pinfunction "VIN_1") (pintype "input"))
      (node (ref "ISP") (pin "2") (pinfunction "VCC_2") (pintype "power_in"))
      (node (ref "J1") (pin "VBUS") (pinfunction "VBUS_VBUS") (pintype "bidirectional"))
      (node (ref "JP10") (pin "2") (pinfunction "2_2") (pintype "passive"))
      (node (ref "JP11") (pin "2") (pinfunction "2_2") (pintype "passive"))
      (node (ref "JP12") (pin "2") (pinfunction "2_2") (pintype "passive"))
      (node (ref "JP13") (pin "2") (pinfunction "2_2") (pintype "passive"))
      (node (ref "JP14") (pin "2") (pinfunction "2_2") (pintype "passive"))
      (node (ref "JP15") (pin "2") (pinfunction "2_2") (pintype "passive"))
      (node (ref "JP16") (pin "2") (pinfunction "2_2") (pintype "passive"))
      (node (ref "JP17") (pin "2") (pinfunction "2_2") (pintype "passive"))
      (node (ref "JP18") (pin "2") (pinfunction "2_2") (pintype "passive"))
      (node (ref "JP19") (pin "2") (pinfunction "2_2") (pintype "passive"))
      (node (ref "JP20") (pin "2") (pinfunction "2_2") (pintype "passive"))
      (node (ref "JP21") (pin "2") (pinfunction "2_2") (pintype "passive"))
      (node (ref "JP22") (pin "2") (pinfunction "2_2") (pintype "passive"))
      (node (ref "JP24") (pin "2") (pinfunction "2_2") (pintype "passive"))
      (node (ref "JP9") (pin "2") (pinfunction "2_2") (pintype "passive"))
      (node (ref "LM7805") (pin "OUT") (pinfunction "OUT_OUT") (pintype "output"))
      (node (ref "P1") (pin "VDD") (pinfunction "VDD_VDD") (pintype "power_in"))
      (node (ref "P2") (pin "VDD") (pinfunction "VDD_VDD") (pintype "power_in"))
      (node (ref "P3") (pin "VDD") (pinfunction "VDD_VDD") (pintype "power_in"))
      (node (ref "P4") (pin "VDD") (pinfunction "VDD_VDD") (pintype "power_in"))
      (node (ref "P5") (pin "VDD") (pinfunction "VDD_VDD") (pintype "power_in"))
      (node (ref "R1") (pin "2") (pinfunction "2_2") (pintype "passive"))
      (node (ref "R10") (pin "2") (pinfunction "2_2") (pintype "passive"))
      (node (ref "R12") (pin "2") (pinfunction "2_2") (pintype "passive"))
      (node (ref "R15") (pin "1") (pinfunction "1_1") (pintype "passive"))
      (node (ref "R16") (pin "1") (pinfunction "1_1") (pintype "passive"))
      (node (ref "R17") (pin "1") (pinfunction "1_1") (pintype "passive"))
      (node (ref "R18") (pin "1") (pinfunction "1_1") (pintype "passive"))
      (node (ref "R20") (pin "2") (pinfunction "2_2") (pintype "passive"))
      (node (ref "R22") (pin "1") (pinfunction "1_1") (pintype "passive"))
      (node (ref "R9") (pin "2") (pinfunction "2_2") (pintype "passive"))
      (node (ref "X-STOP") (pin "2") (pinfunction "2_2") (pintype "passive"))
      (node (ref "Y-STOP") (pin "2") (pinfunction "2_2") (pintype "passive"))
      (node (ref "Z-STOP") (pin "2") (pinfunction "2_2") (pintype "passive"))
    )
    (net (code "53") (name "12V") (class "Default")
      (node (ref "C1") (pin "+") (pinfunction "+_+") (pintype "passive"))
      (node (ref "C12") (pin "1") (pinfunction "+_1") (pintype "passive"))
      (node (ref "C2") (pin "+") (pinfunction "+_+") (pintype "passive"))
      (node (ref "C20") (pin "+") (pinfunction "+_+") (pintype "passive"))
      (node (ref "C3") (pin "+") (pinfunction "+_+") (pintype "passive"))
      (node (ref "C4") (pin "+") (pinfunction "+_+") (pintype "passive"))
      (node (ref "C5") (pin "2") (pinfunction "2_2") (pintype "passive"))
      (node (ref "EXP1") (pin "15") (pinfunction "15_15") (pintype "passive"))
      (node (ref "FAN") (pin "1") (pinfunction "1_1") (pintype "passive"))
      (node (ref "FAN1") (pin "1") (pinfunction "1_1") (pintype "passive"))
      (node (ref "HOTBED") (pin "1") (pinfunction "1_1") (pintype "passive"))
      (node (ref "HOTEND-0") (pin "1") (pinfunction "1_1") (pintype "passive"))
      (node (ref "HOTEND-1") (pin "1") (pinfunction "1_1") (pintype "passive"))
      (node (ref "JP2") (pin "1") (pinfunction "1_1") (pintype "passive"))
      (node (ref "JP23") (pin "1") (pinfunction "1_1") (pintype "passive"))
      (node (ref "JP4") (pin "1") (pinfunction "1_1") (pintype "passive"))
      (node (ref "JP6") (pin "1") (pinfunction "1_1") (pintype "passive"))
      (node (ref "LM7805") (pin "IN") (pinfunction "IN_IN") (pintype "input"))
      (node (ref "P1") (pin "VMOT") (pinfunction "VMOT_VMOT") (pintype "power_in"))
      (node (ref "P2") (pin "VMOT") (pinfunction "VMOT_VMOT") (pintype "power_in"))
      (node (ref "P3") (pin "VMOT") (pinfunction "VMOT_VMOT") (pintype "power_in"))
      (node (ref "P4") (pin "VMOT") (pinfunction "VMOT_VMOT") (pintype "power_in"))
      (node (ref "P5") (pin "VMOT") (pinfunction "VMOT_VMOT") (pintype "power_in"))
      (node (ref "R23") (pin "1") (pinfunction "1_1") (pintype "passive"))
      (node (ref "R24") (pin "1") (pinfunction "1_1") (pintype "passive"))
      (node (ref "R25") (pin "1") (pinfunction "1_1") (pintype "passive"))
      (node (ref "R26") (pin "1") (pinfunction "1_1") (pintype "passive"))
      (node (ref "R27") (pin "2") (pinfunction "2_2") (pintype "passive"))
      (node (ref "R30") (pin "1") (pinfunction "1_1") (pintype "passive"))
    )
    (net (code "54") (name "GND") (class "Default")
      (node (ref "12V") (pin "C") (pinfunction "C_C") (pintype "passive"))
      (node (ref "3V3") (pin "C") (pinfunction "C_C") (pintype "passive"))
      (node (ref "5V") (pin "C") (pinfunction "C_C") (pintype "passive"))
      (node (ref "AT90USB1287") (pin "22") (pinfunction "GND_22") (pintype "power_in"))
      (node (ref "AT90USB1287") (pin "53") (pinfunction "GND_53") (pintype "power_in"))
      (node (ref "AT90USB1287") (pin "6") (pinfunction "UGND_6") (pintype "power_in"))
      (node (ref "AT90USB1287") (pin "63") (pinfunction "AGND_63") (pintype "power_in"))
      (node (ref "B-THERM") (pin "2") (pinfunction "2_2") (pintype "passive"))
      (node (ref "C1") (pin "-") (pinfunction "-_-") (pintype "passive"))
      (node (ref "C10") (pin "1") (pinfunction "1_1") (pintype "passive"))
      (node (ref "C11") (pin "1") (pinfunction "1_1") (pintype "passive"))
      (node (ref "C12") (pin "2") (pinfunction "-_2") (pintype "passive"))
      (node (ref "C13") (pin "1") (pinfunction "1_1") (pintype "passive"))
      (node (ref "C14") (pin "2") (pinfunction "2_2") (pintype "passive"))
      (node (ref "C15") (pin "2") (pinfunction "2_2") (pintype "passive"))
      (node (ref "C16") (pin "2") (pinfunction "-_2") (pintype "passive"))
      (node (ref "C17") (pin "1") (pinfunction "1_1") (pintype "passive"))
      (node (ref "C19") (pin "1") (pinfunction "1_1") (pintype "passive"))
      (node (ref "C2") (pin "-") (pinfunction "-_-") (pintype "passive"))
      (node (ref "C20") (pin "-") (pinfunction "-_-") (pintype "passive"))
      (node (ref "C3") (pin "-") (pinfunction "-_-") (pintype "passive"))
      (node (ref "C4") (pin "-") (pinfunction "-_-") (pintype "passive"))
      (node (ref "C5") (pin "1") (pinfunction "1_1") (pintype "passive"))
      (node (ref "C6") (pin "1") (pinfunction "1_1") (pintype "passive"))
      (node (ref "C7") (pin "1") (pinfunction "1_1") (pintype "passive"))
      (node (ref "C8") (pin "2") (pinfunction "2_2") (pintype "passive"))
      (node (ref "C9") (pin "1") (pinfunction "1_1") (pintype "passive"))
      (node (ref "E0-THERM") (pin "2") (pinfunction "2_2") (pintype "passive"))
      (node (ref "E1-THERM") (pin "2") (pinfunction "2_2") (pintype "passive"))
      (node (ref "EXP1") (pin "14") (pinfunction "14_14") (pintype "passive"))
      (node (ref "EXP1") (pin "16") (pinfunction "16_16") (pintype "passive"))
      (node (ref "IC1") (pin "2") (pinfunction "GND_2") (pintype "passive"))
      (node (ref "IC1") (pin "4") (pinfunction "GND_4") (pintype "passive"))
      (node (ref "IC3") (pin "8") (pinfunction "VSS_8") (pintype "power_in"))
      (node (ref "ISP") (pin "6") (pinfunction "GND_6") (pintype "power_in"))
      (node (ref "J1") (pin "GND") (pinfunction "GND_GND") (pintype "bidirectional"))
      (node (ref "JP2") (pin "2") (pinfunction "2_2") (pintype "passive"))
      (node (ref "JP23") (pin "2") (pinfunction "2_2") (pintype "passive"))
      (node (ref "JP4") (pin "2") (pinfunction "2_2") (pintype "passive"))
      (node (ref "JP6") (pin "2") (pinfunction "2_2") (pintype "passive"))
      (node (ref "LM7805") (pin "GND") (pinfunction "GND_GND") (pintype "input"))
      (node (ref "MICRO-SD") (pin "6") (pinfunction "VSS_6") (pintype "power_in"))
      (node (ref "MICRO-SD") (pin "MT1") (pinfunction "GND_MT1") (pintype "power_in"))
      (node (ref "MICRO-SD") (pin "MT2") (pinfunction "GND1_MT2") (pintype "power_in"))
      (node (ref "P1") (pin "GNDMOT") (pinfunction "GNDMOT_GNDMOT") (pintype "power_in"))
      (node (ref "P1") (pin "GNDVDD") (pinfunction "GNDVDD_GNDVDD") (pintype "power_in"))
      (node (ref "P2") (pin "GNDMOT") (pinfunction "GNDMOT_GNDMOT") (pintype "power_in"))
      (node (ref "P2") (pin "GNDVDD") (pinfunction "GNDVDD_GNDVDD") (pintype "power_in"))
      (node (ref "P3") (pin "GNDMOT") (pinfunction "GNDMOT_GNDMOT") (pintype "power_in"))
      (node (ref "P3") (pin "GNDVDD") (pinfunction "GNDVDD_GNDVDD") (pintype "power_in"))
      (node (ref "P4") (pin "GNDMOT") (pinfunction "GNDMOT_GNDMOT") (pintype "power_in"))
      (node (ref "P4") (pin "GNDVDD") (pinfunction "GNDVDD_GNDVDD") (pintype "power_in"))
      (node (ref "P5") (pin "GNDMOT") (pinfunction "GNDMOT_GNDMOT") (pintype "power_in"))
      (node (ref "P5") (pin "GNDVDD") (pinfunction "GNDVDD_GNDVDD") (pintype "power_in"))
      (node (ref "Q1") (pin "3") (pinfunction "S_3") (pintype "passive"))
      (node (ref "Q2") (pin "3") (pinfunction "S_3") (pintype "passive"))
      (node (ref "Q3") (pin "2") (pinfunction "S_2") (pintype "passive"))
      (node (ref "Q5") (pin "3") (pinfunction "S_3") (pintype "passive"))
      (node (ref "Q6") (pin "2") (pinfunction "S_2") (pintype "passive"))
      (node (ref "R11") (pin "2") (pinfunction "2_2") (pintype "passive"))
      (node (ref "R13") (pin "2") (pinfunction "2_2") (pintype "passive"))
      (node (ref "R14") (pin "2") (pinfunction "2_2") (pintype "passive"))
      (node (ref "R19") (pin "2") (pinfunction "2_2") (pintype "passive"))
      (node (ref "R2") (pin "2") (pinfunction "2_2") (pintype "passive"))
      (node (ref "R21") (pin "2") (pinfunction "2_2") (pintype "passive"))
      (node (ref "R29") (pin "2") (pinfunction "2_2") (pintype "passive"))
      (node (ref "R3") (pin "2") (pinfunction "2_2") (pintype "passive"))
      (node (ref "R4") (pin "2") (pinfunction "2_2") (pintype "passive"))
      (node (ref "R5") (pin "2") (pinfunction "2_2") (pintype "passive"))
      (node (ref "R6") (pin "2") (pinfunction "2_2") (pintype "passive"))
      (node (ref "RESET") (pin "1") (pinfunction "1_1") (pintype "passive"))
      (node (ref "RESET") (pin "2") (pinfunction "2_2") (pintype "passive"))
      (node (ref "U$47") (pin "GND") (pinfunction "GND-SCREW_GND") (pintype "bidirectional"))
      (node (ref "U$48") (pin "GND") (pinfunction "GND-SCREW_GND") (pintype "bidirectional"))
      (node (ref "U$49") (pin "GND") (pinfunction "GND-SCREW_GND") (pintype "bidirectional"))
      (node (ref "U$50") (pin "GND") (pinfunction "GND-SCREW_GND") (pintype "bidirectional"))
      (node (ref "X-STOP") (pin "3") (pinfunction "3_3") (pintype "passive"))
      (node (ref "Y-STOP") (pin "3") (pinfunction "3_3") (pintype "passive"))
      (node (ref "Z-STOP") (pin "3") (pinfunction "3_3") (pintype "passive"))
    )
    (net (code "55") (name "Net-(3V3-PadA)") (class "Default")
      (node (ref "3V3") (pin "A") (pinfunction "A_A") (pintype "passive"))
      (node (ref "R28") (pin "1") (pinfunction "1_1") (pintype "passive"))
    )
    (net (code "56") (name "Net-(5V-PadA)") (class "Default")
      (node (ref "5V") (pin "A") (pinfunction "A_A") (pintype "passive"))
      (node (ref "R1") (pin "1") (pinfunction "1_1") (pintype "passive"))
    )
    (net (code "57") (name "Net-(12V-PadA)") (class "Default")
      (node (ref "12V") (pin "A") (pinfunction "A_A") (pintype "passive"))
      (node (ref "R27") (pin "1") (pinfunction "1_1") (pintype "passive"))
    )
    (net (code "58") (name "Net-(AT90USB1287-D+)") (class "Default")
      (node (ref "AT90USB1287") (pin "5") (pinfunction "D+_5") (pintype "bidirectional"))
      (node (ref "R8") (pin "2") (pinfunction "2_2") (pintype "passive"))
    )
    (net (code "59") (name "Net-(AT90USB1287-D-)") (class "Default")
      (node (ref "AT90USB1287") (pin "4") (pinfunction "D-_4") (pintype "bidirectional"))
      (node (ref "R7") (pin "2") (pinfunction "2_2") (pintype "passive"))
    )
    (net (code "60") (name "Net-(AT90USB1287-PE3_IUID)") (class "Default")
      (node (ref "AT90USB1287") (pin "9") (pinfunction "PE3_IUID_9") (pintype "bidirectional"))
      (node (ref "JP34") (pin "1") (pinfunction "1_1") (pintype "passive"))
    )
    (net (code "61") (name "Net-(AT90USB1287-UCAP)") (class "Default")
      (node (ref "AT90USB1287") (pin "7") (pinfunction "UCAP_7") (pintype "power_in"))
      (node (ref "C11") (pin "2") (pinfunction "2_2") (pintype "passive"))
    )
    (net (code "62") (name "Net-(IC3A-O)") (class "Default")
      (node (ref "IC3") (pin "2") (pinfunction "O_2") (pintype "output"))
      (node (ref "MICRO-SD") (pin "2") (pinfunction "CS_2") (pintype "input"))
    )
    (net (code "63") (name "Net-(IC3B-O)") (class "Default")
      (node (ref "IC3") (pin "4") (pinfunction "O_4") (pintype "output"))
      (node (ref "MICRO-SD") (pin "3") (pinfunction "DATA_IN_3") (pintype "input"))
    )
    (net (code "64") (name "Net-(IC3C-O)") (class "Default")
      (node (ref "IC3") (pin "6") (pinfunction "O_6") (pintype "output"))
      (node (ref "MICRO-SD") (pin "5") (pinfunction "SCLK_5") (pintype "input"))
    )
    (net (code "65") (name "Net-(J1-PadD+)") (class "Default")
      (node (ref "J1") (pin "D+") (pinfunction "D+_D+") (pintype "bidirectional"))
      (node (ref "R8") (pin "1") (pinfunction "1_1") (pintype "passive"))
    )
    (net (code "66") (name "Net-(J1-PadD-)") (class "Default")
      (node (ref "J1") (pin "D-") (pinfunction "D-_D-") (pintype "bidirectional"))
      (node (ref "R7") (pin "1") (pinfunction "1_1") (pintype "passive"))
    )
    (net (code "67") (name "Net-(JP9-Pad1)") (class "Default")
      (node (ref "JP9") (pin "1") (pinfunction "1_1") (pintype "passive"))
      (node (ref "P3") (pin "MS3") (pinfunction "MS3_MS3") (pintype "input"))
    )
    (net (code "68") (name "Net-(JP10-Pad1)") (class "Default")
      (node (ref "JP10") (pin "1") (pinfunction "1_1") (pintype "passive"))
      (node (ref "P3") (pin "MS2") (pinfunction "MS2_MS2") (pintype "input"))
    )
    (net (code "69") (name "Net-(JP11-Pad1)") (class "Default")
      (node (ref "JP11") (pin "1") (pinfunction "1_1") (pintype "passive"))
      (node (ref "P3") (pin "MS1") (pinfunction "MS1_MS1") (pintype "input"))
      (node (ref "R4") (pin "1") (pinfunction "1_1") (pintype "passive"))
    )
    (net (code "70") (name "Net-(JP12-Pad1)") (class "Default")
      (node (ref "JP12") (pin "1") (pinfunction "1_1") (pintype "passive"))
      (node (ref "P2") (pin "MS1") (pinfunction "MS1_MS1") (pintype "input"))
      (node (ref "R3") (pin "1") (pinfunction "1_1") (pintype "passive"))
    )
    (net (code "71") (name "Net-(JP13-Pad1)") (class "Default")
      (node (ref "JP13") (pin "1") (pinfunction "1_1") (pintype "passive"))
      (node (ref "P2") (pin "MS2") (pinfunction "MS2_MS2") (pintype "input"))
    )
    (net (code "72") (name "Net-(JP14-Pad1)") (class "Default")
      (node (ref "JP14") (pin "1") (pinfunction "1_1") (pintype "passive"))
      (node (ref "P2") (pin "MS3") (pinfunction "MS3_MS3") (pintype "input"))
    )
    (net (code "73") (name "Net-(JP15-Pad1)") (class "Default")
      (node (ref "JP15") (pin "1") (pinfunction "1_1") (pintype "passive"))
      (node (ref "P4") (pin "MS2") (pinfunction "MS2_MS2") (pintype "input"))
    )
    (net (code "74") (name "Net-(JP16-Pad1)") (class "Default")
      (node (ref "JP16") (pin "1") (pinfunction "1_1") (pintype "passive"))
      (node (ref "P4") (pin "MS1") (pinfunction "MS1_MS1") (pintype "input"))
      (node (ref "R5") (pin "1") (pinfunction "1_1") (pintype "passive"))
    )
    (net (code "75") (name "Net-(JP17-Pad1)") (class "Default")
      (node (ref "JP17") (pin "1") (pinfunction "1_1") (pintype "passive"))
      (node (ref "P5") (pin "MS3") (pinfunction "MS3_MS3") (pintype "input"))
    )
    (net (code "76") (name "Net-(JP18-Pad1)") (class "Default")
      (node (ref "JP18") (pin "1") (pinfunction "1_1") (pintype "passive"))
      (node (ref "P5") (pin "MS2") (pinfunction "MS2_MS2") (pintype "input"))
    )
    (net (code "77") (name "Net-(JP19-Pad1)") (class "Default")
      (node (ref "JP19") (pin "1") (pinfunction "1_1") (pintype "passive"))
      (node (ref "P5") (pin "MS1") (pinfunction "MS1_MS1") (pintype "input"))
      (node (ref "R21") (pin "1") (pinfunction "1_1") (pintype "passive"))
    )
    (net (code "78") (name "Net-(JP20-Pad1)") (class "Default")
      (node (ref "JP20") (pin "1") (pinfunction "1_1") (pintype "passive"))
      (node (ref "P1") (pin "MS3") (pinfunction "MS3_MS3") (pintype "input"))
    )
    (net (code "79") (name "Net-(JP21-Pad1)") (class "Default")
      (node (ref "JP21") (pin "1") (pinfunction "1_1") (pintype "passive"))
      (node (ref "P4") (pin "MS3") (pinfunction "MS3_MS3") (pintype "input"))
    )
    (net (code "80") (name "Net-(JP22-Pad1)") (class "Default")
      (node (ref "JP22") (pin "1") (pinfunction "1_1") (pintype "passive"))
      (node (ref "P1") (pin "MS2") (pinfunction "MS2_MS2") (pintype "input"))
    )
    (net (code "81") (name "Net-(JP24-Pad1)") (class "Default")
      (node (ref "JP24") (pin "1") (pinfunction "1_1") (pintype "passive"))
      (node (ref "P1") (pin "MS1") (pinfunction "MS1_MS1") (pintype "input"))
      (node (ref "R2") (pin "1") (pinfunction "1_1") (pintype "passive"))
    )
    (net (code "82") (name "Net-(LED1-PadA)") (class "Default")
      (node (ref "LED1") (pin "A") (pinfunction "A_A") (pintype "passive"))
      (node (ref "R30") (pin "2") (pinfunction "2_2") (pintype "passive"))
    )
    (net (code "83") (name "Net-(LED2-PadA)") (class "Default")
      (node (ref "LED2") (pin "A") (pinfunction "A_A") (pintype "passive"))
      (node (ref "R23") (pin "2") (pinfunction "2_2") (pintype "passive"))
    )
    (net (code "84") (name "Net-(LED3-PadA)") (class "Default")
      (node (ref "LED3") (pin "A") (pinfunction "A_A") (pintype "passive"))
      (node (ref "R24") (pin "2") (pinfunction "2_2") (pintype "passive"))
    )
    (net (code "85") (name "Net-(LED4-PadA)") (class "Default")
      (node (ref "LED4") (pin "A") (pinfunction "A_A") (pintype "passive"))
      (node (ref "R25") (pin "2") (pinfunction "2_2") (pintype "passive"))
    )
    (net (code "86") (name "Net-(LED5-PadA)") (class "Default")
      (node (ref "LED5") (pin "A") (pinfunction "A_A") (pintype "passive"))
      (node (ref "R26") (pin "2") (pinfunction "2_2") (pintype "passive"))
    )
    (net (code "87") (name "Net-(P1-MOT-1A)") (class "Default")
      (node (ref "JP1") (pin "3") (pinfunction "3_3") (pintype "passive"))
      (node (ref "P1") (pin "1A") (pinfunction "MOT-1A_1A") (pintype "power_in"))
    )
    (net (code "88") (name "Net-(P1-MOT-1B)") (class "Default")
      (node (ref "JP1") (pin "4") (pinfunction "4_4") (pintype "passive"))
      (node (ref "P1") (pin "1B") (pinfunction "MOT-1B_1B") (pintype "power_in"))
    )
    (net (code "89") (name "Net-(P1-MOT-2A)") (class "Default")
      (node (ref "JP1") (pin "2") (pinfunction "2_2") (pintype "passive"))
      (node (ref "P1") (pin "2A") (pinfunction "MOT-2A_2A") (pintype "power_in"))
    )
    (net (code "90") (name "Net-(P1-MOT-2B)") (class "Default")
      (node (ref "JP1") (pin "1") (pinfunction "1_1") (pintype "passive"))
      (node (ref "P1") (pin "2B") (pinfunction "MOT-2B_2B") (pintype "power_in"))
    )
    (net (code "91") (name "Net-(P1-~{RESET})") (class "Default")
      (node (ref "P1") (pin "!RST") (pinfunction "~{RESET}_!RST") (pintype "input"))
      (node (ref "P1") (pin "!SLP") (pinfunction "~{SLEEP}_!SLP") (pintype "input"))
    )
    (net (code "92") (name "Net-(P2-MOT-1A)") (class "Default")
      (node (ref "JP3") (pin "3") (pinfunction "3_3") (pintype "passive"))
      (node (ref "P2") (pin "1A") (pinfunction "MOT-1A_1A") (pintype "power_in"))
    )
    (net (code "93") (name "Net-(P2-MOT-1B)") (class "Default")
      (node (ref "JP3") (pin "4") (pinfunction "4_4") (pintype "passive"))
      (node (ref "P2") (pin "1B") (pinfunction "MOT-1B_1B") (pintype "power_in"))
    )
    (net (code "94") (name "Net-(P2-MOT-2A)") (class "Default")
      (node (ref "JP3") (pin "2") (pinfunction "2_2") (pintype "passive"))
      (node (ref "P2") (pin "2A") (pinfunction "MOT-2A_2A") (pintype "power_in"))
    )
    (net (code "95") (name "Net-(P2-MOT-2B)") (class "Default")
      (node (ref "JP3") (pin "1") (pinfunction "1_1") (pintype "passive"))
      (node (ref "P2") (pin "2B") (pinfunction "MOT-2B_2B") (pintype "power_in"))
    )
    (net (code "96") (name "Net-(P2-~{RESET})") (class "Default")
      (node (ref "P2") (pin "!RST") (pinfunction "~{RESET}_!RST") (pintype "input"))
      (node (ref "P2") (pin "!SLP") (pinfunction "~{SLEEP}_!SLP") (pintype "input"))
    )
    (net (code "97") (name "Net-(P3-MOT-1A)") (class "Default")
      (node (ref "JP35") (pin "3") (pinfunction "3_3") (pintype "passive"))
      (node (ref "P3") (pin "1A") (pinfunction "MOT-1A_1A") (pintype "power_in"))
    )
    (net (code "98") (name "Net-(P3-MOT-1B)") (class "Default")
      (node (ref "JP35") (pin "4") (pinfunction "4_4") (pintype "passive"))
      (node (ref "P3") (pin "1B") (pinfunction "MOT-1B_1B") (pintype "power_in"))
    )
    (net (code "99") (name "Net-(P3-MOT-2A)") (class "Default")
      (node (ref "JP35") (pin "2") (pinfunction "2_2") (pintype "passive"))
      (node (ref "P3") (pin "2A") (pinfunction "MOT-2A_2A") (pintype "power_in"))
    )
    (net (code "100") (name "Net-(P3-MOT-2B)") (class "Default")
      (node (ref "JP35") (pin "1") (pinfunction "1_1") (pintype "passive"))
      (node (ref "P3") (pin "2B") (pinfunction "MOT-2B_2B") (pintype "power_in"))
    )
    (net (code "101") (name "Net-(P3-~{RESET})") (class "Default")
      (node (ref "P3") (pin "!RST") (pinfunction "~{RESET}_!RST") (pintype "input"))
      (node (ref "P3") (pin "!SLP") (pinfunction "~{SLEEP}_!SLP") (pintype "input"))
    )
    (net (code "102") (name "Net-(P4-MOT-1A)") (class "Default")
      (node (ref "JP7") (pin "3") (pinfunction "3_3") (pintype "passive"))
      (node (ref "P4") (pin "1A") (pinfunction "MOT-1A_1A") (pintype "power_in"))
    )
    (net (code "103") (name "Net-(P4-MOT-1B)") (class "Default")
      (node (ref "JP7") (pin "4") (pinfunction "4_4") (pintype "passive"))
      (node (ref "P4") (pin "1B") (pinfunction "MOT-1B_1B") (pintype "power_in"))
    )
    (net (code "104") (name "Net-(P4-MOT-2A)") (class "Default")
      (node (ref "JP7") (pin "2") (pinfunction "2_2") (pintype "passive"))
      (node (ref "P4") (pin "2A") (pinfunction "MOT-2A_2A") (pintype "power_in"))
    )
    (net (code "105") (name "Net-(P4-MOT-2B)") (class "Default")
      (node (ref "JP7") (pin "1") (pinfunction "1_1") (pintype "passive"))
      (node (ref "P4") (pin "2B") (pinfunction "MOT-2B_2B") (pintype "power_in"))
    )
    (net (code "106") (name "Net-(P4-~{RESET})") (class "Default")
      (node (ref "P4") (pin "!RST") (pinfunction "~{RESET}_!RST") (pintype "input"))
      (node (ref "P4") (pin "!SLP") (pinfunction "~{SLEEP}_!SLP") (pintype "input"))
    )
    (net (code "107") (name "Net-(P5-MOT-1A)") (class "Default")
      (node (ref "JP37") (pin "3") (pinfunction "3_3") (pintype "passive"))
      (node (ref "P5") (pin "1A") (pinfunction "MOT-1A_1A") (pintype "power_in"))
    )
    (net (code "108") (name "Net-(P5-MOT-1B)") (class "Default")
      (node (ref "JP37") (pin "4") (pinfunction "4_4") (pintype "passive"))
      (node (ref "P5") (pin "1B") (pinfunction "MOT-1B_1B") (pintype "power_in"))
    )
    (net (code "109") (name "Net-(P5-MOT-2A)") (class "Default")
      (node (ref "JP37") (pin "2") (pinfunction "2_2") (pintype "passive"))
      (node (ref "P5") (pin "2A") (pinfunction "MOT-2A_2A") (pintype "power_in"))
    )
    (net (code "110") (name "Net-(P5-MOT-2B)") (class "Default")
      (node (ref "JP37") (pin "1") (pinfunction "1_1") (pintype "passive"))
      (node (ref "P5") (pin "2B") (pinfunction "MOT-2B_2B") (pintype "power_in"))
    )
    (net (code "111") (name "Net-(P5-~{RESET})") (class "Default")
      (node (ref "P5") (pin "!RST") (pinfunction "~{RESET}_!RST") (pintype "input"))
      (node (ref "P5") (pin "!SLP") (pinfunction "~{SLEEP}_!SLP") (pintype "input"))
    )
    (net (code "112") (name "Net-(Q1-D)") (class "Default")
      (node (ref "HOTEND-0") (pin "2") (pinfunction "2_2") (pintype "passive"))
      (node (ref "LED4") (pin "C") (pinfunction "C_C") (pintype "passive"))
      (node (ref "Q1") (pin "2") (pinfunction "D_2") (pintype "passive"))
    )
    (net (code "113") (name "Net-(Q2-D)") (class "Default")
      (node (ref "HOTBED") (pin "2") (pinfunction "2_2") (pintype "passive"))
      (node (ref "LED5") (pin "C") (pinfunction "C_C") (pintype "passive"))
      (node (ref "Q2") (pin "2") (pinfunction "D_2") (pintype "passive"))
    )
    (net (code "114") (name "Net-(Q3-D)") (class "Default")
      (node (ref "FAN") (pin "2") (pinfunction "2_2") (pintype "passive"))
      (node (ref "LED2") (pin "C") (pinfunction "C_C") (pintype "passive"))
      (node (ref "Q3") (pin "3") (pinfunction "D_3") (pintype "passive"))
    )
    (net (code "115") (name "Net-(Q6-D)") (class "Default")
      (node (ref "FAN1") (pin "2") (pinfunction "2_2") (pintype "passive"))
      (node (ref "LED1") (pin "C") (pinfunction "C_C") (pintype "passive"))
      (node (ref "Q6") (pin "3") (pinfunction "D_3") (pintype "passive"))
    )
    (net (code "116") (name "unconnected-(AT90USB1287-PE4_INT4_TOSC1-Pad18)") (class "Default")
      (node (ref "AT90USB1287") (pin "18") (pinfunction "PE4_INT4_TOSC1_18") (pintype "bidirectional"))
    )
    (net (code "117") (name "unconnected-(MICRO-SD-CARD_DETECT1-PadCD2)") (class "Default")
      (node (ref "MICRO-SD") (pin "CD2") (pinfunction "CARD_DETECT1_CD2") (pintype "passive"))
    )
    (net (code "118") (name "unconnected-(MICRO-SD-DAT1-Pad8)") (class "Default")
      (node (ref "MICRO-SD") (pin "8") (pinfunction "DAT1_8") (pintype "bidirectional"))
    )
    (net (code "119") (name "unconnected-(MICRO-SD-DAT2-Pad1)") (class "Default")
      (node (ref "MICRO-SD") (pin "1") (pinfunction "DAT2_1") (pintype "bidirectional"))
    )
  )
)
